# Simon.net
KiCad netlist of a schematic drawn in EAGLE
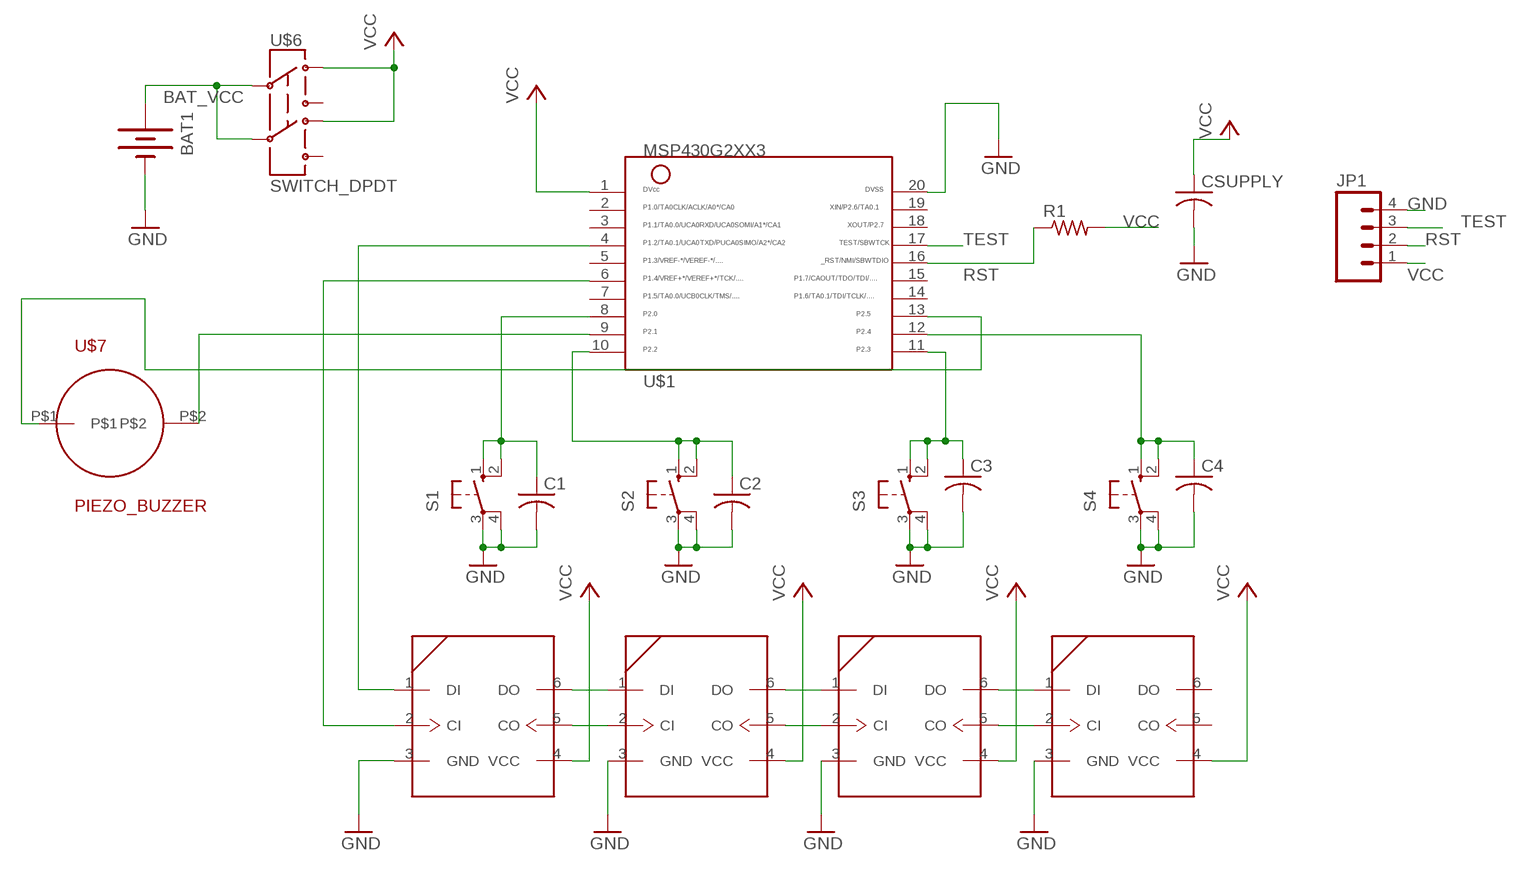
[diagram p0: schematic, sheet 1]

(export (version "E")
  (design (tool "Eeschema 10.0.6"))
  (components
    (comp (ref "BAT1")
      (value "BATTERY")
      (footprint "eagle-import:BATTERY_PACK_2AA")
      (libsource (lib "eagle-import") (part "BATTERY"))
    )
    (comp (ref "C1")
      (value "C-USC1206")
      (footprint "eagle-import:C1206")
      (libsource (lib "eagle-import") (part "C-USC1206"))
    )
    (comp (ref "C2")
      (value "C-USC1206")
      (footprint "eagle-import:C1206")
      (libsource (lib "eagle-import") (part "C-USC1206"))
    )
    (comp (ref "C3")
      (value "C-USC1206")
      (footprint "eagle-import:C1206")
      (libsource (lib "eagle-import") (part "C-USC1206"))
    )
    (comp (ref "C4")
      (value "C-USC1206")
      (footprint "eagle-import:C1206")
      (libsource (lib "eagle-import") (part "C-USC1206"))
    )
    (comp (ref "CSUPPLY")
      (value "C-USC1206")
      (footprint "eagle-import:C1206")
      (libsource (lib "eagle-import") (part "C-USC1206"))
    )
    (comp (ref "JP1")
      (value "M04LOCK")
      (footprint "eagle-import:1X04_LOCK")
      (libsource (lib "eagle-import") (part "M04LOCK"))
    )
    (comp (ref "LED1")
      (value "APA102")
      (footprint "eagle-import:5050")
      (libsource (lib "eagle-import") (part "APA102"))
    )
    (comp (ref "LED2")
      (value "APA102")
      (footprint "eagle-import:5050")
      (libsource (lib "eagle-import") (part "APA102"))
    )
    (comp (ref "LED3")
      (value "APA102")
      (footprint "eagle-import:5050")
      (libsource (lib "eagle-import") (part "APA102"))
    )
    (comp (ref "LED4")
      (value "APA102")
      (footprint "eagle-import:5050")
      (libsource (lib "eagle-import") (part "APA102"))
    )
    (comp (ref "R1")
      (value "R-US_R1206")
      (footprint "eagle-import:R1206")
      (libsource (lib "eagle-import") (part "R-US_R1206"))
    )
    (comp (ref "S1")
      (value "10-XX")
      (footprint "eagle-import:B3F-10XX")
      (fields (field (name "MPN") "B3F-1000"))
      (libsource (lib "eagle-import") (part "10-XX"))
    )
    (comp (ref "S2")
      (value "10-XX")
      (footprint "eagle-import:B3F-10XX")
      (fields (field (name "MPN") "B3F-1000"))
      (libsource (lib "eagle-import") (part "10-XX"))
    )
    (comp (ref "S3")
      (value "10-XX")
      (footprint "eagle-import:B3F-10XX")
      (fields (field (name "MPN") "B3F-1000"))
      (libsource (lib "eagle-import") (part "10-XX"))
    )
    (comp (ref "S4")
      (value "10-XX")
      (footprint "eagle-import:B3F-10XX")
      (fields (field (name "MPN") "B3F-1000"))
      (libsource (lib "eagle-import") (part "10-XX"))
    )
    (comp (ref "U$1")
      (value "MSP430G2XX3TSSOP")
      (footprint "eagle-import:PW20")
      (libsource (lib "eagle-import") (part "MSP430G2XX3TSSOP"))
    )
    (comp (ref "U$6")
      (value "SWITCH_DPDT")
      (footprint "eagle-import:JS_DPDT_TH")
      (libsource (lib "eagle-import") (part "SWITCH_DPDT"))
    )
    (comp (ref "U$7")
      (value "PIEZO_BUZZER")
      (footprint "eagle-import:PIEZO_BUZZER")
      (libsource (lib "eagle-import") (part "PIEZO_BUZZER"))
    )
  )
  (nets
    (net (code "1") (name "/BAT_VCC") (class "Default")
      (node (ref "BAT1") (pin "3V") (pinfunction "+_3V") (pintype "power_in"))
      (node (ref "U$6") (pin "2") (pinfunction "2_2") (pintype "bidirectional"))
      (node (ref "U$6") (pin "5") (pinfunction "5_5") (pintype "bidirectional"))
    )
    (net (code "2") (name "/RST") (class "Default")
      (node (ref "JP1") (pin "2") (pinfunction "2_2") (pintype "passive"))
      (node (ref "R1") (pin "1") (pinfunction "1_1") (pintype "passive"))
      (node (ref "U$1") (pin "16") (pinfunction "16_16") (pintype "bidirectional"))
    )
    (net (code "3") (name "/TEST") (class "Default")
      (node (ref "JP1") (pin "3") (pinfunction "3_3") (pintype "passive"))
      (node (ref "U$1") (pin "17") (pinfunction "17_17") (pintype "bidirectional"))
    )
    (net (code "4") (name "GND") (class "Default")
      (node (ref "BAT1") (pin "GND") (pinfunction "-_GND") (pintype "power_in"))
      (node (ref "C1") (pin "2") (pinfunction "2_2") (pintype "passive"))
      (node (ref "C2") (pin "2") (pinfunction "2_2") (pintype "passive"))
      (node (ref "C3") (pin "2") (pinfunction "2_2") (pintype "passive"))
      (node (ref "C4") (pin "2") (pinfunction "2_2") (pintype "passive"))
      (node (ref "CSUPPLY") (pin "2") (pinfunction "2_2") (pintype "passive"))
      (node (ref "JP1") (pin "4") (pinfunction "4_4") (pintype "passive"))
      (node (ref "LED1") (pin "3") (pinfunction "GND_3") (pintype "power_in"))
      (node (ref "LED2") (pin "3") (pinfunction "GND_3") (pintype "power_in"))
      (node (ref "LED3") (pin "3") (pinfunction "GND_3") (pintype "power_in"))
      (node (ref "LED4") (pin "3") (pinfunction "GND_3") (pintype "power_in"))
      (node (ref "S1") (pin "3") (pinfunction "P_3") (pintype "passive"))
      (node (ref "S1") (pin "4") (pinfunction "P1_4") (pintype "passive"))
      (node (ref "S2") (pin "3") (pinfunction "P_3") (pintype "passive"))
      (node (ref "S2") (pin "4") (pinfunction "P1_4") (pintype "passive"))
      (node (ref "S3") (pin "3") (pinfunction "P_3") (pintype "passive"))
      (node (ref "S3") (pin "4") (pinfunction "P1_4") (pintype "passive"))
      (node (ref "S4") (pin "3") (pinfunction "P_3") (pintype "passive"))
      (node (ref "S4") (pin "4") (pinfunction "P1_4") (pintype "passive"))
      (node (ref "U$1") (pin "20") (pinfunction "20_20") (pintype "bidirectional"))
    )
    (net (code "5") (name "Net-(LED1-CI)") (class "Default")
      (node (ref "LED1") (pin "2") (pinfunction "CI_2") (pintype "input"))
      (node (ref "U$1") (pin "6") (pinfunction "6_6") (pintype "bidirectional"))
    )
    (net (code "6") (name "Net-(LED1-CO)") (class "Default")
      (node (ref "LED1") (pin "5") (pinfunction "CO_5") (pintype "output"))
      (node (ref "LED2") (pin "2") (pinfunction "CI_2") (pintype "input"))
    )
    (net (code "7") (name "Net-(LED1-DI)") (class "Default")
      (node (ref "LED1") (pin "1") (pinfunction "DI_1") (pintype "input"))
      (node (ref "U$1") (pin "4") (pinfunction "4_4") (pintype "bidirectional"))
    )
    (net (code "8") (name "Net-(LED1-DO)") (class "Default")
      (node (ref "LED1") (pin "6") (pinfunction "DO_6") (pintype "output"))
      (node (ref "LED2") (pin "1") (pinfunction "DI_1") (pintype "input"))
    )
    (net (code "9") (name "Net-(LED2-CO)") (class "Default")
      (node (ref "LED2") (pin "5") (pinfunction "CO_5") (pintype "output"))
      (node (ref "LED3") (pin "2") (pinfunction "CI_2") (pintype "input"))
    )
    (net (code "10") (name "Net-(LED2-DO)") (class "Default")
      (node (ref "LED2") (pin "6") (pinfunction "DO_6") (pintype "output"))
      (node (ref "LED3") (pin "1") (pinfunction "DI_1") (pintype "input"))
    )
    (net (code "11") (name "Net-(LED3-CO)") (class "Default")
      (node (ref "LED3") (pin "5") (pinfunction "CO_5") (pintype "output"))
      (node (ref "LED4") (pin "2") (pinfunction "CI_2") (pintype "input"))
    )
    (net (code "12") (name "Net-(LED3-DO)") (class "Default")
      (node (ref "LED3") (pin "6") (pinfunction "DO_6") (pintype "output"))
      (node (ref "LED4") (pin "1") (pinfunction "DI_1") (pintype "input"))
    )
    (net (code "13") (name "Net-(S1-S)") (class "Default")
      (node (ref "C1") (pin "1") (pinfunction "1_1") (pintype "passive"))
      (node (ref "S1") (pin "1") (pinfunction "S_1") (pintype "passive"))
      (node (ref "S1") (pin "2") (pinfunction "S1_2") (pintype "passive"))
      (node (ref "U$1") (pin "8") (pinfunction "8_8") (pintype "bidirectional"))
    )
    (net (code "14") (name "Net-(S2-S)") (class "Default")
      (node (ref "C2") (pin "1") (pinfunction "1_1") (pintype "passive"))
      (node (ref "S2") (pin "1") (pinfunction "S_1") (pintype "passive"))
      (node (ref "S2") (pin "2") (pinfunction "S1_2") (pintype "passive"))
      (node (ref "U$1") (pin "10") (pinfunction "10_10") (pintype "bidirectional"))
    )
    (net (code "15") (name "Net-(S3-S)") (class "Default")
      (node (ref "C3") (pin "1") (pinfunction "1_1") (pintype "passive"))
      (node (ref "S3") (pin "1") (pinfunction "S_1") (pintype "passive"))
      (node (ref "S3") (pin "2") (pinfunction "S1_2") (pintype "passive"))
      (node (ref "U$1") (pin "11") (pinfunction "11_11") (pintype "bidirectional"))
    )
    (net (code "16") (name "Net-(S4-S)") (class "Default")
      (node (ref "C4") (pin "1") (pinfunction "1_1") (pintype "passive"))
      (node (ref "S4") (pin "1") (pinfunction "S_1") (pintype "passive"))
      (node (ref "S4") (pin "2") (pinfunction "S1_2") (pintype "passive"))
      (node (ref "U$1") (pin "12") (pinfunction "12_12") (pintype "bidirectional"))
    )
    (net (code "17") (name "Net-(U$1-Pad9)") (class "Default")
      (node (ref "U$1") (pin "9") (pinfunction "9_9") (pintype "bidirectional"))
      (node (ref "U$7") (pin "P$2") (pinfunction "P$2_P$2") (pintype "bidirectional"))
    )
    (net (code "18") (name "Net-(U$1-Pad13)") (class "Default")
      (node (ref "U$1") (pin "13") (pinfunction "13_13") (pintype "bidirectional"))
      (node (ref "U$7") (pin "P$1") (pinfunction "P$1_P$1") (pintype "bidirectional"))
    )
    (net (code "19") (name "VCC") (class "Default")
      (node (ref "CSUPPLY") (pin "1") (pinfunction "1_1") (pintype "passive"))
      (node (ref "JP1") (pin "1") (pinfunction "1_1") (pintype "passive"))
      (node (ref "LED1") (pin "4") (pinfunction "VCC_4") (pintype "power_in"))
      (node (ref "LED2") (pin "4") (pinfunction "VCC_4") (pintype "power_in"))
      (node (ref "LED3") (pin "4") (pinfunction "VCC_4") (pintype "power_in"))
      (node (ref "LED4") (pin "4") (pinfunction "VCC_4") (pintype "power_in"))
      (node (ref "R1") (pin "2") (pinfunction "2_2") (pintype "passive"))
      (node (ref "U$1") (pin "1") (pinfunction "1_1") (pintype "bidirectional"))
      (node (ref "U$6") (pin "1") (pinfunction "1_1") (pintype "bidirectional"))
      (node (ref "U$6") (pin "4") (pinfunction "4_4") (pintype "bidirectional"))
    )
    (net (code "20") (name "unconnected-(LED4-CO-Pad5)") (class "Default")
      (node (ref "LED4") (pin "5") (pinfunction "CO_5") (pintype "output"))
    )
    (net (code "21") (name "unconnected-(LED4-DO-Pad6)") (class "Default")
      (node (ref "LED4") (pin "6") (pinfunction "DO_6") (pintype "output"))
    )
    (net (code "22") (name "unconnected-(U$1-Pad2)") (class "Default")
      (node (ref "U$1") (pin "2") (pinfunction "2_2") (pintype "bidirectional"))
    )
    (net (code "23") (name "unconnected-(U$1-Pad3)") (class "Default")
      (node (ref "U$1") (pin "3") (pinfunction "3_3") (pintype "bidirectional"))
    )
    (net (code "24") (name "unconnected-(U$1-Pad5)") (class "Default")
      (node (ref "U$1") (pin "5") (pinfunction "5_5") (pintype "bidirectional"))
    )
    (net (code "25") (name "unconnected-(U$1-Pad7)") (class "Default")
      (node (ref "U$1") (pin "7") (pinfunction "7_7") (pintype "bidirectional"))
    )
    (net (code "26") (name "unconnected-(U$1-Pad14)") (class "Default")
      (node (ref "U$1") (pin "14") (pinfunction "14_14") (pintype "bidirectional"))
    )
    (net (code "27") (name "unconnected-(U$1-Pad15)") (class "Default")
      (node (ref "U$1") (pin "15") (pinfunction "15_15") (pintype "bidirectional"))
    )
    (net (code "28") (name "unconnected-(U$1-Pad18)") (class "Default")
      (node (ref "U$1") (pin "18") (pinfunction "18_18") (pintype "bidirectional"))
    )
    (net (code "29") (name "unconnected-(U$1-Pad19)") (class "Default")
      (node (ref "U$1") (pin "19") (pinfunction "19_19") (pintype "bidirectional"))
    )
    (net (code "30") (name "unconnected-(U$6-Pad3)") (class "Default")
      (node (ref "U$6") (pin "3") (pinfunction "3_3") (pintype "bidirectional"))
    )
    (net (code "31") (name "unconnected-(U$6-Pad6)") (class "Default")
      (node (ref "U$6") (pin "6") (pinfunction "6_6") (pintype "bidirectional"))
    )
  )
)
